# adc.net
KiCad netlist of a schematic drawn in Altium Designer
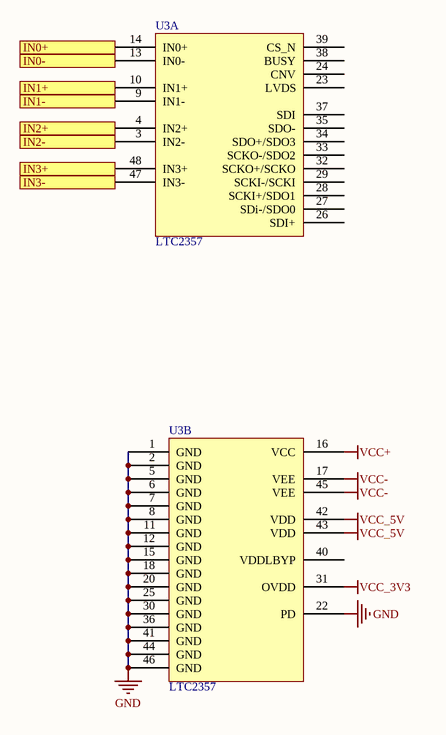
[diagram p0: adc.SchDoc]

(export (version "E")
  (design (tool "Eeschema 10.0.6"))
  (components
    (comp (ref "U3") (value "LTC2357") (footprint "LTC2357") (libsource (lib "Tauv-Lib") (part "LTC2357")))
  )
  (nets
    (net (code "1") (name "/IN0+") (class "Default")
      (node (ref "U3") (pin "14") (pinfunction "IN0+_14") (pintype "passive"))
    )
    (net (code "2") (name "/IN0-") (class "Default")
      (node (ref "U3") (pin "13") (pinfunction "IN0-_13") (pintype "passive"))
    )
    (net (code "3") (name "/IN1+") (class "Default")
      (node (ref "U3") (pin "10") (pinfunction "IN1+_10") (pintype "passive"))
    )
    (net (code "4") (name "/IN1-") (class "Default")
      (node (ref "U3") (pin "9") (pinfunction "IN1-_9") (pintype "passive"))
    )
    (net (code "5") (name "/IN2+") (class "Default")
      (node (ref "U3") (pin "4") (pinfunction "IN2+_4") (pintype "passive"))
    )
    (net (code "6") (name "/IN2-") (class "Default")
      (node (ref "U3") (pin "3") (pinfunction "IN2-_3") (pintype "passive"))
    )
    (net (code "7") (name "/IN3+") (class "Default")
      (node (ref "U3") (pin "48") (pinfunction "IN3+_48") (pintype "passive"))
    )
    (net (code "8") (name "/IN3-") (class "Default")
      (node (ref "U3") (pin "47") (pinfunction "IN3-_47") (pintype "passive"))
    )
    (net (code "9") (name "GND") (class "Default")
      (node (ref "U3") (pin "1") (pinfunction "GND_1") (pintype "passive"))
      (node (ref "U3") (pin "11") (pinfunction "GND_11") (pintype "passive"))
      (node (ref "U3") (pin "12") (pinfunction "GND_12") (pintype "passive"))
      (node (ref "U3") (pin "15") (pinfunction "GND_15") (pintype "passive"))
      (node (ref "U3") (pin "18") (pinfunction "GND_18") (pintype "passive"))
      (node (ref "U3") (pin "2") (pinfunction "GND_2") (pintype "passive"))
      (node (ref "U3") (pin "20") (pinfunction "GND_20") (pintype "passive"))
      (node (ref "U3") (pin "22") (pinfunction "PD_22") (pintype "passive"))
      (node (ref "U3") (pin "25") (pinfunction "GND_25") (pintype "passive"))
      (node (ref "U3") (pin "30") (pinfunction "GND_30") (pintype "passive"))
      (node (ref "U3") (pin "36") (pinfunction "GND_36") (pintype "passive"))
      (node (ref "U3") (pin "41") (pinfunction "GND_41") (pintype "passive"))
      (node (ref "U3") (pin "44") (pinfunction "GND_44") (pintype "passive"))
      (node (ref "U3") (pin "46") (pinfunction "GND_46") (pintype "passive"))
      (node (ref "U3") (pin "5") (pinfunction "GND_5") (pintype "passive"))
      (node (ref "U3") (pin "6") (pinfunction "GND_6") (pintype "passive"))
      (node (ref "U3") (pin "7") (pinfunction "GND_7") (pintype "passive"))
      (node (ref "U3") (pin "8") (pinfunction "GND_8") (pintype "passive"))
    )
    (net (code "10") (name "VCC+") (class "Default")
      (node (ref "U3") (pin "16") (pinfunction "VCC_16") (pintype "passive"))
    )
    (net (code "11") (name "VCC-") (class "Default")
      (node (ref "U3") (pin "17") (pinfunction "VEE_17") (pintype "passive"))
      (node (ref "U3") (pin "45") (pinfunction "VEE_45") (pintype "passive"))
    )
    (net (code "12") (name "VCC_3V3") (class "Default")
      (node (ref "U3") (pin "31") (pinfunction "OVDD_31") (pintype "passive"))
    )
    (net (code "13") (name "VCC_5V") (class "Default")
      (node (ref "U3") (pin "42") (pinfunction "VDD_42") (pintype "passive"))
      (node (ref "U3") (pin "43") (pinfunction "VDD_43") (pintype "passive"))
    )
    (net (code "14") (name "unconnected-(U3A-BUSY-Pad38)") (class "Default")
      (node (ref "U3") (pin "38") (pinfunction "BUSY_38") (pintype "passive"))
    )
    (net (code "15") (name "unconnected-(U3A-CNV-Pad24)") (class "Default")
      (node (ref "U3") (pin "24") (pinfunction "CNV_24") (pintype "passive"))
    )
    (net (code "16") (name "unconnected-(U3A-CS_N-Pad39)") (class "Default")
      (node (ref "U3") (pin "39") (pinfunction "CS_N_39") (pintype "passive"))
    )
    (net (code "17") (name "unconnected-(U3A-LVDS-Pad23)") (class "Default")
      (node (ref "U3") (pin "23") (pinfunction "LVDS_23") (pintype "passive"))
    )
    (net (code "18") (name "unconnected-(U3A-SCKI+{slash}SDO1-Pad28)") (class "Default")
      (node (ref "U3") (pin "28") (pinfunction "SCKI+/SDO1_28") (pintype "passive"))
    )
    (net (code "19") (name "unconnected-(U3A-SCKI-{slash}SCKI-Pad29)") (class "Default")
      (node (ref "U3") (pin "29") (pinfunction "SCKI-/SCKI_29") (pintype "passive"))
    )
    (net (code "20") (name "unconnected-(U3A-SCKO+{slash}SCKO-Pad32)") (class "Default")
      (node (ref "U3") (pin "32") (pinfunction "SCKO+/SCKO_32") (pintype "passive"))
    )
    (net (code "21") (name "unconnected-(U3A-SCKO-{slash}SDO2-Pad33)") (class "Default")
      (node (ref "U3") (pin "33") (pinfunction "SCKO-/SDO2_33") (pintype "passive"))
    )
    (net (code "22") (name "unconnected-(U3A-SDI+-Pad26)") (class "Default")
      (node (ref "U3") (pin "26") (pinfunction "SDI+_26") (pintype "passive"))
    )
    (net (code "23") (name "unconnected-(U3A-SDI-Pad37)") (class "Default")
      (node (ref "U3") (pin "37") (pinfunction "SDI_37") (pintype "passive"))
    )
    (net (code "24") (name "unconnected-(U3A-SDO+{slash}SDO3-Pad34)") (class "Default")
      (node (ref "U3") (pin "34") (pinfunction "SDO+/SDO3_34") (pintype "passive"))
    )
    (net (code "25") (name "unconnected-(U3A-SDO--Pad35)") (class "Default")
      (node (ref "U3") (pin "35") (pinfunction "SDO-_35") (pintype "passive"))
    )
    (net (code "26") (name "unconnected-(U3A-SDi-{slash}SDO0-Pad27)") (class "Default")
      (node (ref "U3") (pin "27") (pinfunction "SDi-/SDO0_27") (pintype "passive"))
    )
    (net (code "27") (name "unconnected-(U3B-VDDLBYP-Pad40)") (class "Default")
      (node (ref "U3") (pin "40") (pinfunction "VDDLBYP_40") (pintype "passive"))
    )
  )
)
